# 4_MCU.net
KiCad netlist of a schematic drawn in Altium Designer
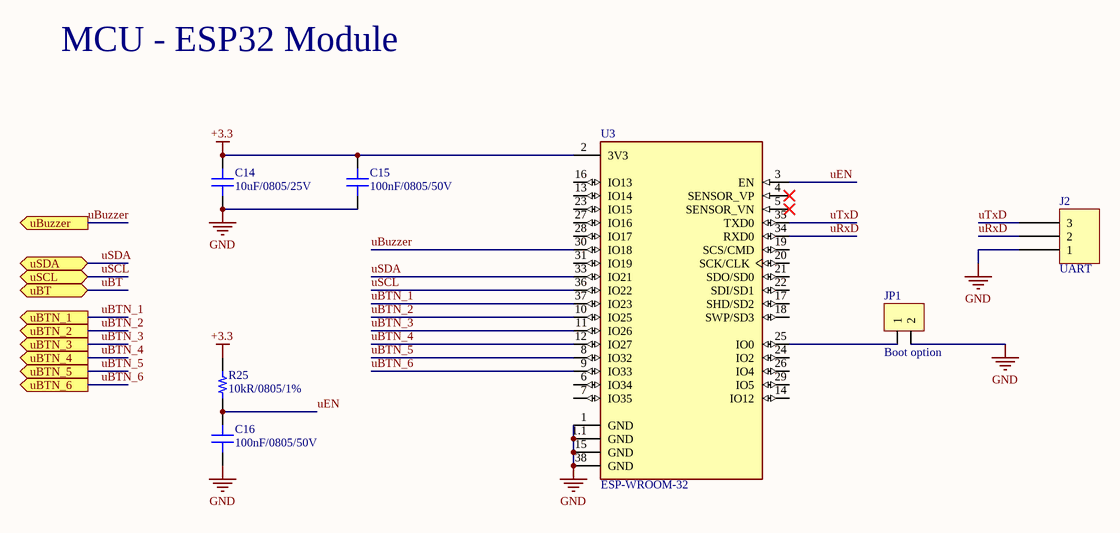
[diagram p0: 4_MCU.SchDoc]

(export (version "E")
  (design (tool "Eeschema 10.0.6"))
  (components
    (comp (ref "C14")
      (value "10uF/0805/25V")
      (footprint "CAP FILM 0805")
      (description "Multilayer Ceramic Capacitor, 10 uF, 25 V, ï¿½ 10%, X5R, 0805 [2012 Metric]")
      (fields
        (field (name "MANUFACTURER") "Samsung")
        (field (name "MANUFACTURER PART NUMBER") "CL21A106KAYNNNE")
      )
      (libsource (lib "NLOC_Altium_Library") (part "Capacitor - MLCC"))
    )
    (comp (ref "C15")
      (value "100nF/0805/50V")
      (footprint "CAP FILM 0805")
      (description "Multilayer Ceramic Capacitor, 0.1 uF, 50 V, ï¿½ 10%, X7R, 0805 [2012 Metric]")
      (fields
        (field (name "MANUFACTURER") "Samsung")
        (field (name "MANUFACTURER PART NUMBER") "CL21B104KBCNNNC")
      )
      (libsource (lib "NLOC_Altium_Library") (part "Capacitor - MLCC"))
    )
    (comp (ref "C16")
      (value "100nF/0805/50V")
      (footprint "CAP FILM 0805")
      (description "Multilayer Ceramic Capacitor, 0.1 uF, 50 V, ï¿½ 10%, X7R, 0805 [2012 Metric]")
      (fields
        (field (name "MANUFACTURER") "Samsung")
        (field (name "MANUFACTURER PART NUMBER") "CL21B104KBCNNNC")
      )
      (libsource (lib "NLOC_Altium_Library") (part "Capacitor - MLCC"))
    )
    (comp (ref "J2")
      (value "UART")
      (footprint "JST B3B-PH-K")
      (libsource (lib "NLOC_Altium_Library") (part "Connector 3 Pin"))
    )
    (comp (ref "JP1")
      (value "Boot option")
      (footprint "JP2-CLOSED")
      (description "WR-PHD 2.54 mm Angled Socket Header")
      (fields
        (field (name "MANUFACTURER") "W¨¹rth Elektronik eiSos GmbH")
        (field (name "PARTNO") "613002143121")
        (field (name "CREATED BY") "Karrer Zheng")
      )
      (libsource (lib "LIBRARYALT") (part "JP2"))
    )
    (comp (ref "R25")
      (value "10kR/0805/1%")
      (footprint "RES 0805_2012")
      (description "SMD Chip Resistor, 10 kOhm, ï¿½ 1%, 125 mW, 0805 [2012 Metric], Thick Film, General Purpose")
      (fields
        (field (name "MANUFACTURER") "Yageo")
        (field (name "MANUFACTURER PART NUMBER") "RC0805FR-0710KL")
      )
      (libsource (lib "NLOC_Altium_Library") (part "Resistor"))
    )
    (comp (ref "U3")
      (value "ESP-WROOM-32")
      (footprint "MODULE_ESP-WROOM-32")
      (fields (field (name "MF") "Espressif Systems"))
      (libsource (lib "ESP-WROOM-32") (part "ESP-WROOM-32"))
    )
  )
  (nets
    (net (code "1") (name "+3.3") (class "Default")
      (node (ref "C14") (pin "2") (pinfunction "2_2") (pintype "passive"))
      (node (ref "C15") (pin "2") (pinfunction "2_2") (pintype "passive"))
      (node (ref "R25") (pin "2") (pinfunction "2_2") (pintype "passive"))
      (node (ref "U3") (pin "2") (pinfunction "3V3_2") (pintype "power_in"))
    )
    (net (code "3") (name "/uBTN_1") (class "Default")
      (node (ref "U3") (pin "37") (pinfunction "IO23_37") (pintype "bidirectional"))
    )
    (net (code "4") (name "/uBTN_2") (class "Default")
      (node (ref "U3") (pin "10") (pinfunction "IO25_10") (pintype "bidirectional"))
    )
    (net (code "5") (name "/uBTN_3") (class "Default")
      (node (ref "U3") (pin "11") (pinfunction "IO26_11") (pintype "bidirectional"))
    )
    (net (code "6") (name "/uBTN_4") (class "Default")
      (node (ref "U3") (pin "12") (pinfunction "IO27_12") (pintype "bidirectional"))
    )
    (net (code "7") (name "/uBTN_5") (class "Default")
      (node (ref "U3") (pin "8") (pinfunction "IO32_8") (pintype "bidirectional"))
    )
    (net (code "8") (name "/uBTN_6") (class "Default")
      (node (ref "U3") (pin "9") (pinfunction "IO33_9") (pintype "bidirectional"))
    )
    (net (code "9") (name "/uBuzzer") (class "Default")
      (node (ref "U3") (pin "30") (pinfunction "IO18_30") (pintype "bidirectional"))
    )
    (net (code "10") (name "/uEN") (class "Default")
      (node (ref "C16") (pin "2") (pinfunction "2_2") (pintype "passive"))
      (node (ref "R25") (pin "1") (pinfunction "1_1") (pintype "passive"))
      (node (ref "U3") (pin "3") (pinfunction "EN_3") (pintype "input"))
    )
    (net (code "11") (name "/uRxD") (class "Default")
      (node (ref "J2") (pin "2") (pinfunction "2_2") (pintype "passive"))
      (node (ref "U3") (pin "34") (pinfunction "RXD0_34") (pintype "bidirectional"))
    )
    (net (code "12") (name "/uSCL") (class "Default")
      (node (ref "U3") (pin "36") (pinfunction "IO22_36") (pintype "bidirectional"))
    )
    (net (code "13") (name "/uSDA") (class "Default")
      (node (ref "U3") (pin "33") (pinfunction "IO21_33") (pintype "bidirectional"))
    )
    (net (code "14") (name "/uTxD") (class "Default")
      (node (ref "J2") (pin "3") (pinfunction "3_3") (pintype "passive"))
      (node (ref "U3") (pin "35") (pinfunction "TXD0_35") (pintype "bidirectional"))
    )
    (net (code "15") (name "GND") (class "Default")
      (node (ref "C14") (pin "1") (pinfunction "1_1") (pintype "passive"))
      (node (ref "C15") (pin "1") (pinfunction "1_1") (pintype "passive"))
      (node (ref "C16") (pin "1") (pinfunction "1_1") (pintype "passive"))
      (node (ref "J2") (pin "1") (pinfunction "1_1") (pintype "passive"))
      (node (ref "JP1") (pin "2") (pinfunction "2_2") (pintype "passive"))
      (node (ref "U3") (pin "1") (pinfunction "GND_1") (pintype "power_in"))
      (node (ref "U3") (pin "1.1") (pinfunction "GND_1.1") (pintype "power_in"))
      (node (ref "U3") (pin "15") (pinfunction "GND_15") (pintype "power_in"))
      (node (ref "U3") (pin "38") (pinfunction "GND_38") (pintype "power_in"))
    )
    (net (code "16") (name "Net-(U3-IO0)") (class "Default")
      (node (ref "JP1") (pin "1") (pinfunction "1_1") (pintype "passive"))
      (node (ref "U3") (pin "25") (pinfunction "IO0_25") (pintype "bidirectional"))
    )
    (net (code "17") (name "unconnected-(U3-IO2-Pad24)") (class "Default")
      (node (ref "U3") (pin "24") (pinfunction "IO2_24") (pintype "bidirectional"))
    )
    (net (code "18") (name "unconnected-(U3-IO4-Pad26)") (class "Default")
      (node (ref "U3") (pin "26") (pinfunction "IO4_26") (pintype "bidirectional"))
    )
    (net (code "19") (name "unconnected-(U3-IO5-Pad29)") (class "Default")
      (node (ref "U3") (pin "29") (pinfunction "IO5_29") (pintype "bidirectional"))
    )
    (net (code "20") (name "unconnected-(U3-IO12-Pad14)") (class "Default")
      (node (ref "U3") (pin "14") (pinfunction "IO12_14") (pintype "bidirectional"))
    )
    (net (code "21") (name "unconnected-(U3-IO13-Pad16)") (class "Default")
      (node (ref "U3") (pin "16") (pinfunction "IO13_16") (pintype "bidirectional"))
    )
    (net (code "22") (name "unconnected-(U3-IO14-Pad13)") (class "Default")
      (node (ref "U3") (pin "13") (pinfunction "IO14_13") (pintype "bidirectional"))
    )
    (net (code "23") (name "unconnected-(U3-IO15-Pad23)") (class "Default")
      (node (ref "U3") (pin "23") (pinfunction "IO15_23") (pintype "bidirectional"))
    )
    (net (code "24") (name "unconnected-(U3-IO16-Pad27)") (class "Default")
      (node (ref "U3") (pin "27") (pinfunction "IO16_27") (pintype "bidirectional"))
    )
    (net (code "25") (name "unconnected-(U3-IO17-Pad28)") (class "Default")
      (node (ref "U3") (pin "28") (pinfunction "IO17_28") (pintype "bidirectional"))
    )
    (net (code "26") (name "unconnected-(U3-IO19-Pad31)") (class "Default")
      (node (ref "U3") (pin "31") (pinfunction "IO19_31") (pintype "bidirectional"))
    )
    (net (code "27") (name "unconnected-(U3-IO34-Pad6)") (class "Default")
      (node (ref "U3") (pin "6") (pinfunction "IO34_6") (pintype "bidirectional"))
    )
    (net (code "28") (name "unconnected-(U3-IO35-Pad7)") (class "Default")
      (node (ref "U3") (pin "7") (pinfunction "IO35_7") (pintype "bidirectional"))
    )
    (net (code "29") (name "unconnected-(U3-SCK{slash}CLK-Pad20)") (class "Default")
      (node (ref "U3") (pin "20") (pinfunction "SCK/CLK_20") (pintype "bidirectional"))
    )
    (net (code "30") (name "unconnected-(U3-SCS{slash}CMD-Pad19)") (class "Default")
      (node (ref "U3") (pin "19") (pinfunction "SCS/CMD_19") (pintype "bidirectional"))
    )
    (net (code "31") (name "unconnected-(U3-SDI{slash}SD1-Pad22)") (class "Default")
      (node (ref "U3") (pin "22") (pinfunction "SDI/SD1_22") (pintype "bidirectional"))
    )
    (net (code "32") (name "unconnected-(U3-SDO{slash}SD0-Pad21)") (class "Default")
      (node (ref "U3") (pin "21") (pinfunction "SDO/SD0_21") (pintype "bidirectional"))
    )
    (net (code "33") (name "unconnected-(U3-SENSOR_VN-Pad5)") (class "Default")
      (node (ref "U3") (pin "5") (pinfunction "SENSOR_VN_5") (pintype "input+no_connect"))
    )
    (net (code "34") (name "unconnected-(U3-SENSOR_VP-Pad4)") (class "Default")
      (node (ref "U3") (pin "4") (pinfunction "SENSOR_VP_4") (pintype "input+no_connect"))
    )
    (net (code "35") (name "unconnected-(U3-SHD{slash}SD2-Pad17)") (class "Default")
      (node (ref "U3") (pin "17") (pinfunction "SHD/SD2_17") (pintype "bidirectional"))
    )
    (net (code "36") (name "unconnected-(U3-SWP{slash}SD3-Pad18)") (class "Default")
      (node (ref "U3") (pin "18") (pinfunction "SWP/SD3_18") (pintype "bidirectional"))
    )
  )
)
